# power.net
KiCad netlist of a schematic drawn in EAGLE
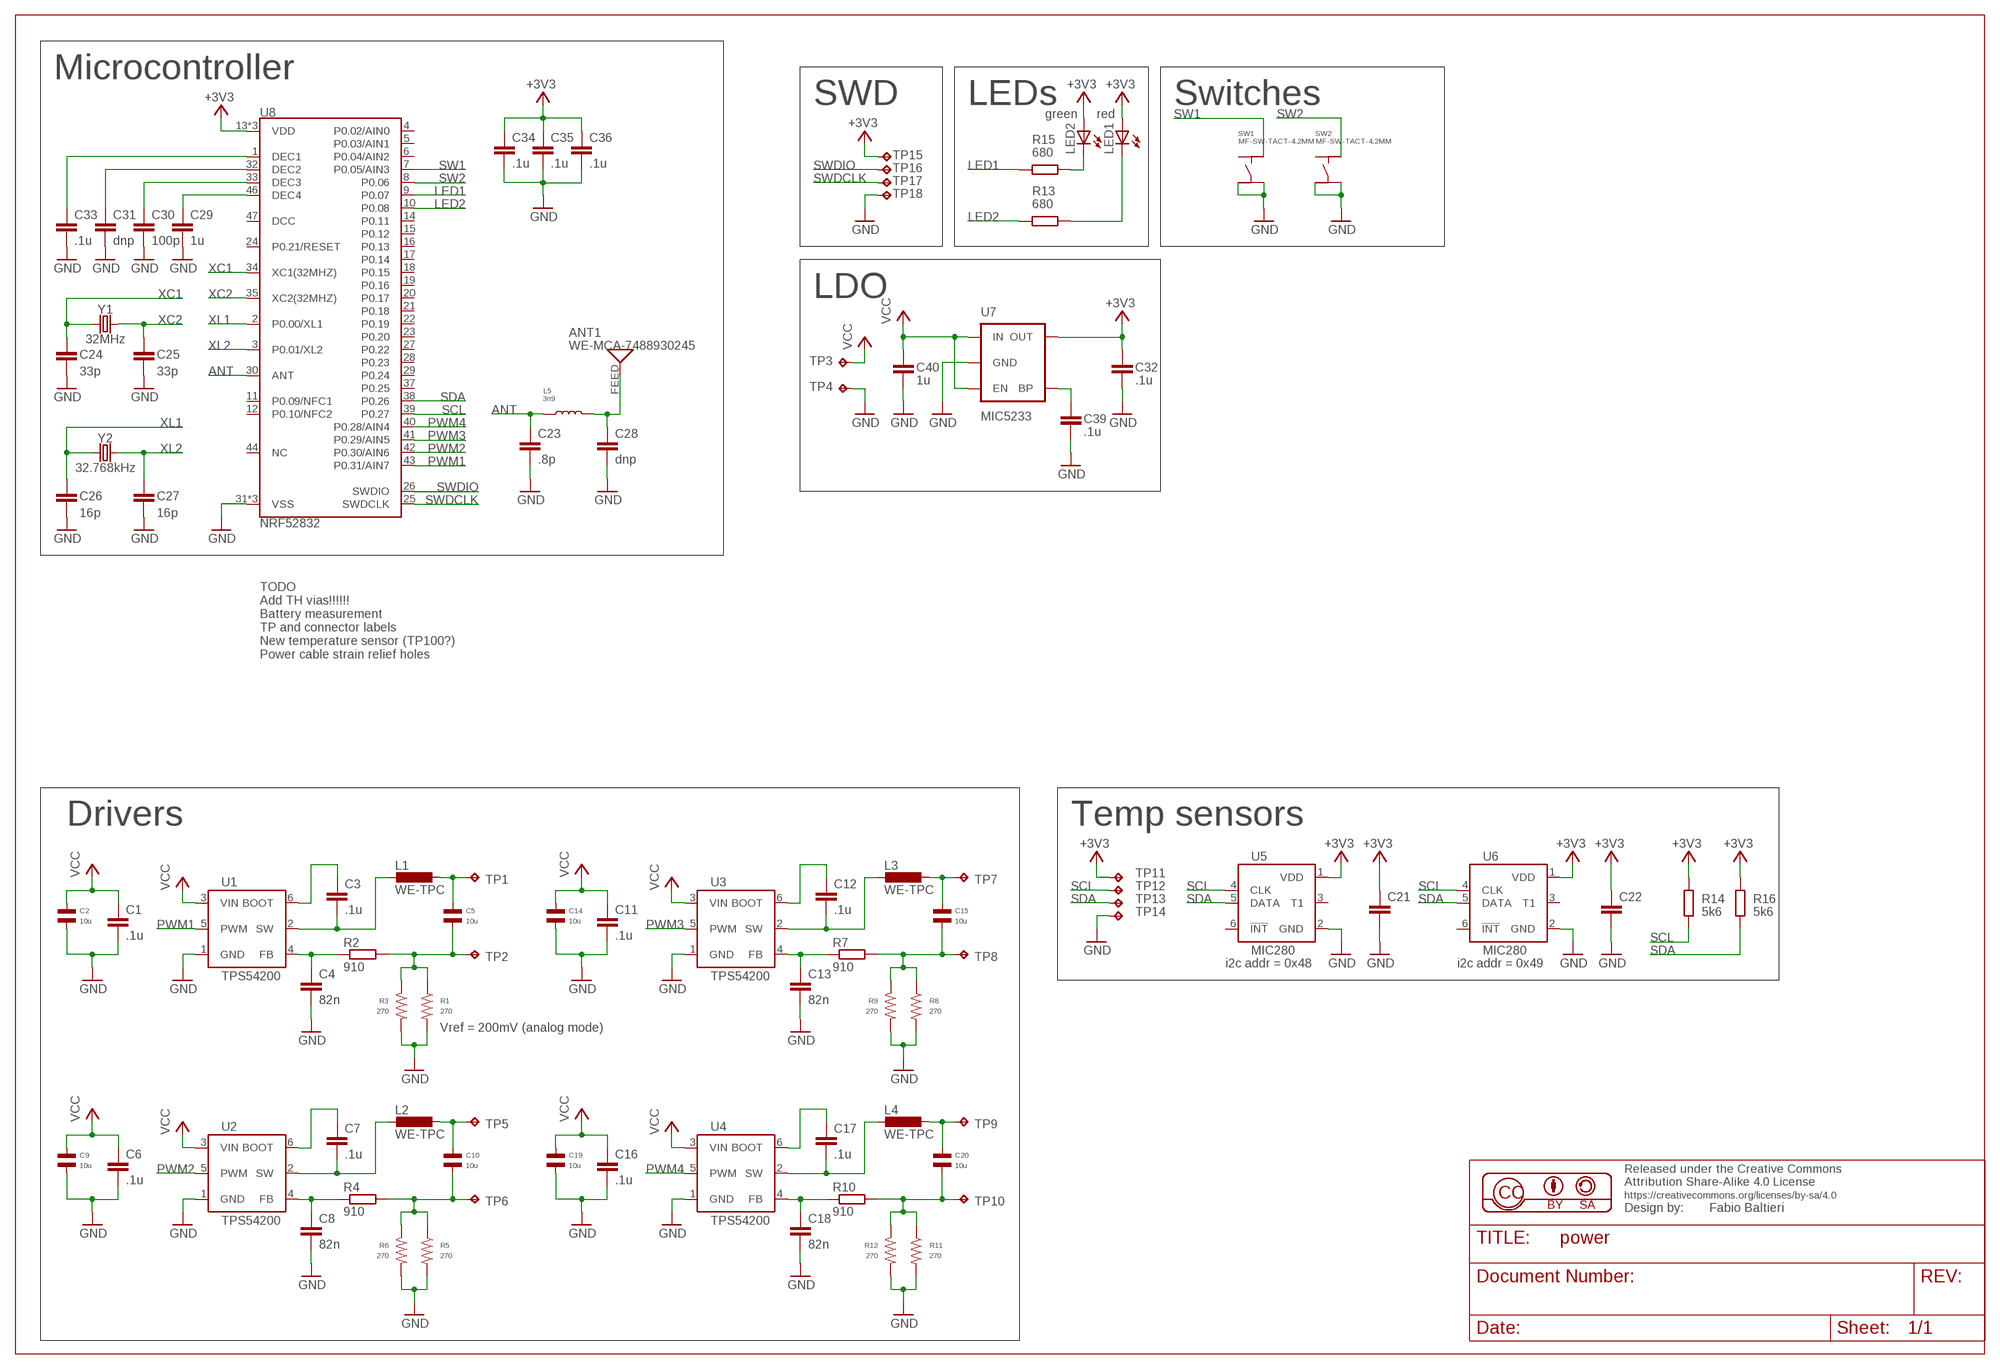
[diagram p0: schematic, sheet 1]

(export (version "E")
  (design (tool "Eeschema 10.0.6"))
  (components
    (comp (ref "ANT1")
      (value "WE-MCA-7488930245")
      (footprint "eagle-import:WE-MCA")
      (libsource (lib "eagle-import") (part "WE-MCA-7488930245"))
    )
    (comp (ref "C1")
      (value ".1u")
      (footprint "eagle-import:0603")
      (libsource (lib "eagle-import") (part "C0603"))
    )
    (comp (ref "C2")
      (value "10u")
      (footprint "eagle-import:C1206")
      (libsource (lib "eagle-import") (part "CAPACITOR_NP_1206"))
    )
    (comp (ref "C3")
      (value ".1u")
      (footprint "eagle-import:0603")
      (libsource (lib "eagle-import") (part "C0603"))
    )
    (comp (ref "C4")
      (value "82n")
      (footprint "eagle-import:0603")
      (libsource (lib "eagle-import") (part "C0603"))
    )
    (comp (ref "C5")
      (value "10u")
      (footprint "eagle-import:C1206")
      (libsource (lib "eagle-import") (part "CAPACITOR_NP_1206"))
    )
    (comp (ref "C6")
      (value ".1u")
      (footprint "eagle-import:0603")
      (libsource (lib "eagle-import") (part "C0603"))
    )
    (comp (ref "C7")
      (value ".1u")
      (footprint "eagle-import:0603")
      (libsource (lib "eagle-import") (part "C0603"))
    )
    (comp (ref "C8")
      (value "82n")
      (footprint "eagle-import:0603")
      (libsource (lib "eagle-import") (part "C0603"))
    )
    (comp (ref "C9")
      (value "10u")
      (footprint "eagle-import:C1206")
      (libsource (lib "eagle-import") (part "CAPACITOR_NP_1206"))
    )
    (comp (ref "C10")
      (value "10u")
      (footprint "eagle-import:C1206")
      (libsource (lib "eagle-import") (part "CAPACITOR_NP_1206"))
    )
    (comp (ref "C11")
      (value ".1u")
      (footprint "eagle-import:0603")
      (libsource (lib "eagle-import") (part "C0603"))
    )
    (comp (ref "C12")
      (value ".1u")
      (footprint "eagle-import:0603")
      (libsource (lib "eagle-import") (part "C0603"))
    )
    (comp (ref "C13")
      (value "82n")
      (footprint "eagle-import:0603")
      (libsource (lib "eagle-import") (part "C0603"))
    )
    (comp (ref "C14")
      (value "10u")
      (footprint "eagle-import:C1206")
      (libsource (lib "eagle-import") (part "CAPACITOR_NP_1206"))
    )
    (comp (ref "C15")
      (value "10u")
      (footprint "eagle-import:C1206")
      (libsource (lib "eagle-import") (part "CAPACITOR_NP_1206"))
    )
    (comp (ref "C16")
      (value ".1u")
      (footprint "eagle-import:0603")
      (libsource (lib "eagle-import") (part "C0603"))
    )
    (comp (ref "C17")
      (value ".1u")
      (footprint "eagle-import:0603")
      (libsource (lib "eagle-import") (part "C0603"))
    )
    (comp (ref "C18")
      (value "82n")
      (footprint "eagle-import:0603")
      (libsource (lib "eagle-import") (part "C0603"))
    )
    (comp (ref "C19")
      (value "10u")
      (footprint "eagle-import:C1206")
      (libsource (lib "eagle-import") (part "CAPACITOR_NP_1206"))
    )
    (comp (ref "C20")
      (value "10u")
      (footprint "eagle-import:C1206")
      (libsource (lib "eagle-import") (part "CAPACITOR_NP_1206"))
    )
    (comp (ref "C21")
      (value "C0603")
      (footprint "eagle-import:0603")
      (libsource (lib "eagle-import") (part "C0603"))
    )
    (comp (ref "C22")
      (value "C0603")
      (footprint "eagle-import:0603")
      (libsource (lib "eagle-import") (part "C0603"))
    )
    (comp (ref "C23")
      (value ".8p")
      (footprint "eagle-import:0603")
      (libsource (lib "eagle-import") (part "C0603"))
    )
    (comp (ref "C24")
      (value "33p")
      (footprint "eagle-import:0603")
      (libsource (lib "eagle-import") (part "C0603"))
    )
    (comp (ref "C25")
      (value "33p")
      (footprint "eagle-import:0603")
      (libsource (lib "eagle-import") (part "C0603"))
    )
    (comp (ref "C26")
      (value "16p")
      (footprint "eagle-import:0603")
      (libsource (lib "eagle-import") (part "C0603"))
    )
    (comp (ref "C27")
      (value "16p")
      (footprint "eagle-import:0603")
      (libsource (lib "eagle-import") (part "C0603"))
    )
    (comp (ref "C28")
      (value "dnp")
      (footprint "eagle-import:0603")
      (libsource (lib "eagle-import") (part "C0603"))
    )
    (comp (ref "C29")
      (value "1u")
      (footprint "eagle-import:0603")
      (libsource (lib "eagle-import") (part "C0603"))
    )
    (comp (ref "C30")
      (value "100p")
      (footprint "eagle-import:0603")
      (libsource (lib "eagle-import") (part "C0603"))
    )
    (comp (ref "C31")
      (value "dnp")
      (footprint "eagle-import:0603")
      (libsource (lib "eagle-import") (part "C0603"))
    )
    (comp (ref "C32")
      (value ".1u")
      (footprint "eagle-import:0603")
      (libsource (lib "eagle-import") (part "C0603"))
    )
    (comp (ref "C33")
      (value ".1u")
      (footprint "eagle-import:0603")
      (libsource (lib "eagle-import") (part "C0603"))
    )
    (comp (ref "C34")
      (value ".1u")
      (footprint "eagle-import:0603")
      (libsource (lib "eagle-import") (part "C0603"))
    )
    (comp (ref "C35")
      (value ".1u")
      (footprint "eagle-import:0603")
      (libsource (lib "eagle-import") (part "C0603"))
    )
    (comp (ref "C36")
      (value ".1u")
      (footprint "eagle-import:0603")
      (libsource (lib "eagle-import") (part "C0603"))
    )
    (comp (ref "C39")
      (value ".1u")
      (footprint "eagle-import:0603")
      (libsource (lib "eagle-import") (part "C0603"))
    )
    (comp (ref "C40")
      (value "1u")
      (footprint "eagle-import:0603")
      (libsource (lib "eagle-import") (part "C0603"))
    )
    (comp (ref "L1")
      (value "WE-TPC")
      (footprint "eagle-import:WE-TPC_INDUCTOR")
      (libsource (lib "eagle-import") (part "WE-TPC"))
    )
    (comp (ref "L2")
      (value "WE-TPC")
      (footprint "eagle-import:WE-TPC_INDUCTOR")
      (libsource (lib "eagle-import") (part "WE-TPC"))
    )
    (comp (ref "L3")
      (value "WE-TPC")
      (footprint "eagle-import:WE-TPC_INDUCTOR")
      (libsource (lib "eagle-import") (part "WE-TPC"))
    )
    (comp (ref "L4")
      (value "WE-TPC")
      (footprint "eagle-import:WE-TPC_INDUCTOR")
      (libsource (lib "eagle-import") (part "WE-TPC"))
    )
    (comp (ref "L5")
      (value "3n9")
      (footprint "eagle-import:L0603")
      (libsource (lib "eagle-import") (part "INDUCTOR_0603"))
    )
    (comp (ref "LED1")
      (value "LEDSML0805")
      (footprint "eagle-import:SML0805")
      (libsource (lib "eagle-import") (part "LEDSML0805"))
    )
    (comp (ref "LED2")
      (value "LEDSML0805")
      (footprint "eagle-import:SML0805")
      (libsource (lib "eagle-import") (part "LEDSML0805"))
    )
    (comp (ref "R1")
      (value "270")
      (footprint "eagle-import:R0805")
      (libsource (lib "eagle-import") (part "RESISTOR_0805"))
    )
    (comp (ref "R2")
      (value "910")
      (footprint "eagle-import:0603")
      (libsource (lib "eagle-import") (part "R0603"))
    )
    (comp (ref "R3")
      (value "270")
      (footprint "eagle-import:R0805")
      (libsource (lib "eagle-import") (part "RESISTOR_0805"))
    )
    (comp (ref "R4")
      (value "910")
      (footprint "eagle-import:0603")
      (libsource (lib "eagle-import") (part "R0603"))
    )
    (comp (ref "R5")
      (value "270")
      (footprint "eagle-import:R0805")
      (libsource (lib "eagle-import") (part "RESISTOR_0805"))
    )
    (comp (ref "R6")
      (value "270")
      (footprint "eagle-import:R0805")
      (libsource (lib "eagle-import") (part "RESISTOR_0805"))
    )
    (comp (ref "R7")
      (value "910")
      (footprint "eagle-import:0603")
      (libsource (lib "eagle-import") (part "R0603"))
    )
    (comp (ref "R8")
      (value "270")
      (footprint "eagle-import:R0805")
      (libsource (lib "eagle-import") (part "RESISTOR_0805"))
    )
    (comp (ref "R9")
      (value "270")
      (footprint "eagle-import:R0805")
      (libsource (lib "eagle-import") (part "RESISTOR_0805"))
    )
    (comp (ref "R10")
      (value "910")
      (footprint "eagle-import:0603")
      (libsource (lib "eagle-import") (part "R0603"))
    )
    (comp (ref "R11")
      (value "270")
      (footprint "eagle-import:R0805")
      (libsource (lib "eagle-import") (part "RESISTOR_0805"))
    )
    (comp (ref "R12")
      (value "270")
      (footprint "eagle-import:R0805")
      (libsource (lib "eagle-import") (part "RESISTOR_0805"))
    )
    (comp (ref "R13")
      (value "680")
      (footprint "eagle-import:0603")
      (libsource (lib "eagle-import") (part "R0603"))
    )
    (comp (ref "R14")
      (value "5k6")
      (footprint "eagle-import:0603")
      (libsource (lib "eagle-import") (part "R0603"))
    )
    (comp (ref "R15")
      (value "680")
      (footprint "eagle-import:0603")
      (libsource (lib "eagle-import") (part "R0603"))
    )
    (comp (ref "R16")
      (value "5k6")
      (footprint "eagle-import:0603")
      (libsource (lib "eagle-import") (part "R0603"))
    )
    (comp (ref "SW1")
      (value "MF-SW-TACT-4.2MM")
      (footprint "eagle-import:TACT4.2MM")
      (fields (field (name "HOUSEPART") "YES"))
      (libsource (lib "eagle-import") (part "TACT_4.2MM"))
    )
    (comp (ref "SW2")
      (value "MF-SW-TACT-4.2MM")
      (footprint "eagle-import:TACT4.2MM")
      (fields (field (name "HOUSEPART") "YES"))
      (libsource (lib "eagle-import") (part "TACT_4.2MM"))
    )
    (comp (ref "TP1")
      (value "TPTP18R")
      (footprint "eagle-import:TP18R")
      (libsource (lib "eagle-import") (part "testpad_385_TPTP18R"))
    )
    (comp (ref "TP2")
      (value "TPTP18R")
      (footprint "eagle-import:TP18R")
      (libsource (lib "eagle-import") (part "testpad_385_TPTP18R"))
    )
    (comp (ref "TP3")
      (value "TPTP18R")
      (footprint "eagle-import:TP18R")
      (libsource (lib "eagle-import") (part "testpad_385_TPTP18R"))
    )
    (comp (ref "TP4")
      (value "TPTP18R")
      (footprint "eagle-import:TP18R")
      (libsource (lib "eagle-import") (part "testpad_385_TPTP18R"))
    )
    (comp (ref "TP5")
      (value "TPTP18R")
      (footprint "eagle-import:TP18R")
      (libsource (lib "eagle-import") (part "testpad_385_TPTP18R"))
    )
    (comp (ref "TP6")
      (value "TPTP18R")
      (footprint "eagle-import:TP18R")
      (libsource (lib "eagle-import") (part "testpad_385_TPTP18R"))
    )
    (comp (ref "TP7")
      (value "TPTP18R")
      (footprint "eagle-import:TP18R")
      (libsource (lib "eagle-import") (part "testpad_385_TPTP18R"))
    )
    (comp (ref "TP8")
      (value "TPTP18R")
      (footprint "eagle-import:TP18R")
      (libsource (lib "eagle-import") (part "testpad_385_TPTP18R"))
    )
    (comp (ref "TP9")
      (value "TPTP18R")
      (footprint "eagle-import:TP18R")
      (libsource (lib "eagle-import") (part "testpad_385_TPTP18R"))
    )
    (comp (ref "TP10")
      (value "TPTP18R")
      (footprint "eagle-import:TP18R")
      (libsource (lib "eagle-import") (part "testpad_385_TPTP18R"))
    )
    (comp (ref "TP11")
      (value "TPTP14R")
      (footprint "eagle-import:TP14R")
      (libsource (lib "eagle-import") (part "testpad_385_TPTP14R"))
    )
    (comp (ref "TP12")
      (value "TPTP14R")
      (footprint "eagle-import:TP14R")
      (libsource (lib "eagle-import") (part "testpad_385_TPTP14R"))
    )
    (comp (ref "TP13")
      (value "TPTP14R")
      (footprint "eagle-import:TP14R")
      (libsource (lib "eagle-import") (part "testpad_385_TPTP14R"))
    )
    (comp (ref "TP14")
      (value "TPTP14R")
      (footprint "eagle-import:TP14R")
      (libsource (lib "eagle-import") (part "testpad_385_TPTP14R"))
    )
    (comp (ref "TP15")
      (value "TPTP12R")
      (footprint "eagle-import:TP12R")
      (libsource (lib "eagle-import") (part "TPTP12R"))
    )
    (comp (ref "TP16")
      (value "TPTP12R")
      (footprint "eagle-import:TP12R")
      (libsource (lib "eagle-import") (part "TPTP12R"))
    )
    (comp (ref "TP17")
      (value "TPTP12R")
      (footprint "eagle-import:TP12R")
      (libsource (lib "eagle-import") (part "TPTP12R"))
    )
    (comp (ref "TP18")
      (value "TPTP12R")
      (footprint "eagle-import:TP12R")
      (libsource (lib "eagle-import") (part "TPTP12R"))
    )
    (comp (ref "U1")
      (value "TPS54200")
      (footprint "eagle-import:SOT23-6L")
      (libsource (lib "eagle-import") (part "TPS54200"))
    )
    (comp (ref "U2")
      (value "TPS54200")
      (footprint "eagle-import:SOT23-6L")
      (libsource (lib "eagle-import") (part "TPS54200"))
    )
    (comp (ref "U3")
      (value "TPS54200")
      (footprint "eagle-import:SOT23-6L")
      (libsource (lib "eagle-import") (part "TPS54200"))
    )
    (comp (ref "U4")
      (value "TPS54200")
      (footprint "eagle-import:SOT23-6L")
      (libsource (lib "eagle-import") (part "TPS54200"))
    )
    (comp (ref "U5")
      (value "MIC280")
      (footprint "eagle-import:SOT23-6L")
      (libsource (lib "eagle-import") (part "MIC280"))
    )
    (comp (ref "U6")
      (value "MIC280")
      (footprint "eagle-import:SOT23-6L")
      (libsource (lib "eagle-import") (part "MIC280"))
    )
    (comp (ref "U7")
      (value "MIC5233")
      (footprint "eagle-import:SOT23-5")
      (libsource (lib "eagle-import") (part "V_REG_LDOSMD"))
    )
    (comp (ref "U8")
      (value "NRF52832")
      (footprint "eagle-import:QFN48-6X6MM")
      (libsource (lib "eagle-import") (part "NRF52832"))
    )
    (comp (ref "Y1")
      (value "32MHz")
      (footprint "eagle-import:CRYSTAL-SMD-3.2X2.5MM")
      (libsource (lib "eagle-import") (part "CRYSTALSMD-3.2X2.5"))
    )
    (comp (ref "Y2")
      (value "32.768kHz")
      (footprint "eagle-import:CRYSTAL-SMD-3.2X1.5MM")
      (libsource (lib "eagle-import") (part "CRYSTAL-32.768KHZSMD-3.2X1.5"))
    )
  )
  (nets
    (net (code "1") (name "+3V3") (class "Default")
      (node (ref "C21") (pin "1") (pinfunction "1_1") (pintype "passive"))
      (node (ref "C22") (pin "1") (pinfunction "1_1") (pintype "passive"))
      (node (ref "C32") (pin "1") (pinfunction "1_1") (pintype "passive"))
      (node (ref "C34") (pin "1") (pinfunction "1_1") (pintype "passive"))
      (node (ref "C35") (pin "1") (pinfunction "1_1") (pintype "passive"))
      (node (ref "C36") (pin "1") (pinfunction "1_1") (pintype "passive"))
      (node (ref "LED1") (pin "A") (pinfunction "A_A") (pintype "passive"))
      (node (ref "LED2") (pin "A") (pinfunction "A_A") (pintype "passive"))
      (node (ref "R14") (pin "1") (pinfunction "1_1") (pintype "passive"))
      (node (ref "R16") (pin "1") (pinfunction "1_1") (pintype "passive"))
      (node (ref "TP11") (pin "TP") (pinfunction "TP_TP") (pintype "input"))
      (node (ref "TP15") (pin "TP") (pinfunction "TP_TP") (pintype "input"))
      (node (ref "U5") (pin "1") (pinfunction "VDD_1") (pintype "bidirectional"))
      (node (ref "U6") (pin "1") (pinfunction "VDD_1") (pintype "bidirectional"))
      (node (ref "U7") (pin "5") (pinfunction "OUT_5") (pintype "passive"))
      (node (ref "U8") (pin "13") (pinfunction "VDD_13") (pintype "bidirectional"))
      (node (ref "U8") (pin "36") (pinfunction "VDD_36") (pintype "bidirectional"))
      (node (ref "U8") (pin "48") (pinfunction "VDD_48") (pintype "bidirectional"))
    )
    (net (code "2") (name "/ANT") (class "Default")
      (node (ref "C23") (pin "1") (pinfunction "1_1") (pintype "passive"))
      (node (ref "L5") (pin "P$1") (pinfunction "P$1_P$1") (pintype "passive"))
      (node (ref "U8") (pin "30") (pinfunction "ANT_30") (pintype "bidirectional"))
    )
    (net (code "3") (name "/LED1") (class "Default")
      (node (ref "R15") (pin "2") (pinfunction "2_2") (pintype "passive"))
      (node (ref "U8") (pin "9") (pinfunction "P0.07_9") (pintype "bidirectional"))
    )
    (net (code "4") (name "/LED2") (class "Default")
      (node (ref "R13") (pin "2") (pinfunction "2_2") (pintype "passive"))
      (node (ref "U8") (pin "10") (pinfunction "P0.08_10") (pintype "bidirectional"))
    )
    (net (code "5") (name "/PWM1") (class "Default")
      (node (ref "U1") (pin "5") (pinfunction "PWM_5") (pintype "bidirectional"))
      (node (ref "U8") (pin "43") (pinfunction "P0.31/AIN7_43") (pintype "bidirectional"))
    )
    (net (code "6") (name "/PWM2") (class "Default")
      (node (ref "U2") (pin "5") (pinfunction "PWM_5") (pintype "bidirectional"))
      (node (ref "U8") (pin "42") (pinfunction "P0.30/AIN6_42") (pintype "bidirectional"))
    )
    (net (code "7") (name "/PWM3") (class "Default")
      (node (ref "U3") (pin "5") (pinfunction "PWM_5") (pintype "bidirectional"))
      (node (ref "U8") (pin "41") (pinfunction "P0.29/AIN5_41") (pintype "bidirectional"))
    )
    (net (code "8") (name "/PWM4") (class "Default")
      (node (ref "U4") (pin "5") (pinfunction "PWM_5") (pintype "bidirectional"))
      (node (ref "U8") (pin "40") (pinfunction "P0.28/AIN4_40") (pintype "bidirectional"))
    )
    (net (code "9") (name "/SCL") (class "Default")
      (node (ref "R14") (pin "2") (pinfunction "2_2") (pintype "passive"))
      (node (ref "TP12") (pin "TP") (pinfunction "TP_TP") (pintype "input"))
      (node (ref "U5") (pin "4") (pinfunction "CLK_4") (pintype "bidirectional"))
      (node (ref "U6") (pin "4") (pinfunction "CLK_4") (pintype "bidirectional"))
      (node (ref "U8") (pin "39") (pinfunction "P0.27_39") (pintype "bidirectional"))
    )
    (net (code "10") (name "/SDA") (class "Default")
      (node (ref "R16") (pin "2") (pinfunction "2_2") (pintype "passive"))
      (node (ref "TP13") (pin "TP") (pinfunction "TP_TP") (pintype "input"))
      (node (ref "U5") (pin "5") (pinfunction "DATA_5") (pintype "bidirectional"))
      (node (ref "U6") (pin "5") (pinfunction "DATA_5") (pintype "bidirectional"))
      (node (ref "U8") (pin "38") (pinfunction "P0.26_38") (pintype "bidirectional"))
    )
    (net (code "11") (name "/SW1") (class "Default")
      (node (ref "SW1") (pin "P$2") (pinfunction "P$2_P$2") (pintype "bidirectional"))
      (node (ref "U8") (pin "7") (pinfunction "P0.05/AIN3_7") (pintype "bidirectional"))
    )
    (net (code "12") (name "/SW2") (class "Default")
      (node (ref "SW2") (pin "P$2") (pinfunction "P$2_P$2") (pintype "bidirectional"))
      (node (ref "U8") (pin "8") (pinfunction "P0.06_8") (pintype "bidirectional"))
    )
    (net (code "13") (name "/SWDCLK") (class "Default")
      (node (ref "TP17") (pin "TP") (pinfunction "TP_TP") (pintype "input"))
      (node (ref "U8") (pin "25") (pinfunction "SWDCLK_25") (pintype "bidirectional"))
    )
    (net (code "14") (name "/SWDIO") (class "Default")
      (node (ref "TP16") (pin "TP") (pinfunction "TP_TP") (pintype "input"))
      (node (ref "U8") (pin "26") (pinfunction "SWDIO_26") (pintype "bidirectional"))
    )
    (net (code "15") (name "/XC1") (class "Default")
      (node (ref "C24") (pin "1") (pinfunction "1_1") (pintype "passive"))
      (node (ref "U8") (pin "34") (pinfunction "XC1(32MHZ)_34") (pintype "bidirectional"))
      (node (ref "Y1") (pin "1") (pinfunction "1_1") (pintype "passive"))
    )
    (net (code "16") (name "/XC2") (class "Default")
      (node (ref "C25") (pin "1") (pinfunction "1_1") (pintype "passive"))
      (node (ref "U8") (pin "35") (pinfunction "XC2(32MHZ)_35") (pintype "bidirectional"))
      (node (ref "Y1") (pin "3") (pinfunction "2_3") (pintype "passive"))
    )
    (net (code "17") (name "/XL1") (class "Default")
      (node (ref "C26") (pin "1") (pinfunction "1_1") (pintype "passive"))
      (node (ref "U8") (pin "2") (pinfunction "P0.00/XL1_2") (pintype "bidirectional"))
      (node (ref "Y2") (pin "P$1") (pinfunction "1_P$1") (pintype "passive"))
    )
    (net (code "18") (name "/XL2") (class "Default")
      (node (ref "C27") (pin "1") (pinfunction "1_1") (pintype "passive"))
      (node (ref "U8") (pin "3") (pinfunction "P0.01/XL2_3") (pintype "bidirectional"))
      (node (ref "Y2") (pin "P$2") (pinfunction "2_P$2") (pintype "passive"))
    )
    (net (code "19") (name "GND") (class "Default")
      (node (ref "C1") (pin "2") (pinfunction "2_2") (pintype "passive"))
      (node (ref "C11") (pin "2") (pinfunction "2_2") (pintype "passive"))
      (node (ref "C13") (pin "2") (pinfunction "2_2") (pintype "passive"))
      (node (ref "C14") (pin "P$2") (pinfunction "P$2_P$2") (pintype "passive"))
      (node (ref "C16") (pin "2") (pinfunction "2_2") (pintype "passive"))
      (node (ref "C18") (pin "2") (pinfunction "2_2") (pintype "passive"))
      (node (ref "C19") (pin "P$2") (pinfunction "P$2_P$2") (pintype "passive"))
      (node (ref "C2") (pin "P$2") (pinfunction "P$2_P$2") (pintype "passive"))
      (node (ref "C21") (pin "2") (pinfunction "2_2") (pintype "passive"))
      (node (ref "C22") (pin "2") (pinfunction "2_2") (pintype "passive"))
      (node (ref "C23") (pin "2") (pinfunction "2_2") (pintype "passive"))
      (node (ref "C24") (pin "2") (pinfunction "2_2") (pintype "passive"))
      (node (ref "C25") (pin "2") (pinfunction "2_2") (pintype "passive"))
      (node (ref "C26") (pin "2") (pinfunction "2_2") (pintype "passive"))
      (node (ref "C27") (pin "2") (pinfunction "2_2") (pintype "passive"))
      (node (ref "C28") (pin "2") (pinfunction "2_2") (pintype "passive"))
      (node (ref "C29") (pin "2") (pinfunction "2_2") (pintype "passive"))
      (node (ref "C30") (pin "2") (pinfunction "2_2") (pintype "passive"))
      (node (ref "C31") (pin "2") (pinfunction "2_2") (pintype "passive"))
      (node (ref "C32") (pin "2") (pinfunction "2_2") (pintype "passive"))
      (node (ref "C33") (pin "2") (pinfunction "2_2") (pintype "passive"))
      (node (ref "C34") (pin "2") (pinfunction "2_2") (pintype "passive"))
      (node (ref "C35") (pin "2") (pinfunction "2_2") (pintype "passive"))
      (node (ref "C36") (pin "2") (pinfunction "2_2") (pintype "passive"))
      (node (ref "C39") (pin "2") (pinfunction "2_2") (pintype "passive"))
      (node (ref "C4") (pin "2") (pinfunction "2_2") (pintype "passive"))
      (node (ref "C40") (pin "2") (pinfunction "2_2") (pintype "passive"))
      (node (ref "C6") (pin "2") (pinfunction "2_2") (pintype "passive"))
      (node (ref "C8") (pin "2") (pinfunction "2_2") (pintype "passive"))
      (node (ref "C9") (pin "P$2") (pinfunction "P$2_P$2") (pintype "passive"))
      (node (ref "R1") (pin "P$2") (pinfunction "P$2_P$2") (pintype "passive"))
      (node (ref "R11") (pin "P$2") (pinfunction "P$2_P$2") (pintype "passive"))
      (node (ref "R12") (pin "P$2") (pinfunction "P$2_P$2") (pintype "passive"))
      (node (ref "R3") (pin "P$2") (pinfunction "P$2_P$2") (pintype "passive"))
      (node (ref "R5") (pin "P$2") (pinfunction "P$2_P$2") (pintype "passive"))
      (node (ref "R6") (pin "P$2") (pinfunction "P$2_P$2") (pintype "passive"))
      (node (ref "R8") (pin "P$2") (pinfunction "P$2_P$2") (pintype "passive"))
      (node (ref "R9") (pin "P$2") (pinfunction "P$2_P$2") (pintype "passive"))
      (node (ref "SW1") (pin "P$3") (pinfunction "P$3_P$3") (pintype "bidirectional"))
      (node (ref "SW1") (pin "P$4") (pinfunction "P$4_P$4") (pintype "bidirectional"))
      (node (ref "SW2") (pin "P$3") (pinfunction "P$3_P$3") (pintype "bidirectional"))
      (node (ref "SW2") (pin "P$4") (pinfunction "P$4_P$4") (pintype "bidirectional"))
      (node (ref "TP14") (pin "TP") (pinfunction "TP_TP") (pintype "input"))
      (node (ref "TP18") (pin "TP") (pinfunction "TP_TP") (pintype "input"))
      (node (ref "TP4") (pin "TP") (pinfunction "TP_TP") (pintype "input"))
      (node (ref "U1") (pin "1") (pinfunction "GND_1") (pintype "bidirectional"))
      (node (ref "U2") (pin "1") (pinfunction "GND_1") (pintype "bidirectional"))
      (node (ref "U3") (pin "1") (pinfunction "GND_1") (pintype "bidirectional"))
      (node (ref "U4") (pin "1") (pinfunction "GND_1") (pintype "bidirectional"))
      (node (ref "U5") (pin "2") (pinfunction "GND_2") (pintype "bidirectional"))
      (node (ref "U6") (pin "2") (pinfunction "GND_2") (pintype "bidirectional"))
      (node (ref "U7") (pin "2") (pinfunction "GND_2") (pintype "input"))
      (node (ref "U8") (pin "31") (pinfunction "VSS_31") (pintype "bidirectional"))
      (node (ref "U8") (pin "45") (pinfunction "VSS_45") (pintype "bidirectional"))
      (node (ref "U8") (pin "EP") (pinfunction "VSS_EP") (pintype "bidirectional"))
    )
    (net (code "20") (name "Net-(ANT1-P$1)") (class "Default")
      (node (ref "ANT1") (pin "FEED") (pinfunction "P$1_FEED") (pintype "bidirectional"))
      (node (ref "C28") (pin "1") (pinfunction "1_1") (pintype "passive"))
      (node (ref "L5") (pin "P$2") (pinfunction "P$2_P$2") (pintype "passive"))
    )
    (net (code "21") (name "Net-(C5-PadP$2)") (class "Default")
      (node (ref "C5") (pin "P$2") (pinfunction "P$2_P$2") (pintype "passive"))
      (node (ref "R1") (pin "P$1") (pinfunction "P$1_P$1") (pintype "passive"))
      (node (ref "R2") (pin "2") (pinfunction "2_2") (pintype "passive"))
      (node (ref "R3") (pin "P$1") (pinfunction "P$1_P$1") (pintype "passive"))
      (node (ref "TP2") (pin "TP") (pinfunction "TP_TP") (pintype "input"))
    )
    (net (code "22") (name "Net-(C10-PadP$2)") (class "Default")
      (node (ref "C10") (pin "P$2") (pinfunction "P$2_P$2") (pintype "passive"))
      (node (ref "R4") (pin "2") (pinfunction "2_2") (pintype "passive"))
      (node (ref "R5") (pin "P$1") (pinfunction "P$1_P$1") (pintype "passive"))
      (node (ref "R6") (pin "P$1") (pinfunction "P$1_P$1") (pintype "passive"))
      (node (ref "TP6") (pin "TP") (pinfunction "TP_TP") (pintype "input"))
    )
    (net (code "23") (name "Net-(C15-PadP$2)") (class "Default")
      (node (ref "C15") (pin "P$2") (pinfunction "P$2_P$2") (pintype "passive"))
      (node (ref "R7") (pin "2") (pinfunction "2_2") (pintype "passive"))
      (node (ref "R8") (pin "P$1") (pinfunction "P$1_P$1") (pintype "passive"))
      (node (ref "R9") (pin "P$1") (pinfunction "P$1_P$1") (pintype "passive"))
      (node (ref "TP8") (pin "TP") (pinfunction "TP_TP") (pintype "input"))
    )
    (net (code "24") (name "Net-(C20-PadP$2)") (class "Default")
      (node (ref "C20") (pin "P$2") (pinfunction "P$2_P$2") (pintype "passive"))
      (node (ref "R10") (pin "2") (pinfunction "2_2") (pintype "passive"))
      (node (ref "R11") (pin "P$1") (pinfunction "P$1_P$1") (pintype "passive"))
      (node (ref "R12") (pin "P$1") (pinfunction "P$1_P$1") (pintype "passive"))
      (node (ref "TP10") (pin "TP") (pinfunction "TP_TP") (pintype "input"))
    )
    (net (code "25") (name "Net-(L1-1)") (class "Default")
      (node (ref "C3") (pin "2") (pinfunction "2_2") (pintype "passive"))
      (node (ref "L1") (pin "P$1") (pinfunction "1_P$1") (pintype "passive"))
      (node (ref "U1") (pin "2") (pinfunction "SW_2") (pintype "bidirectional"))
    )
    (net (code "26") (name "Net-(L1-2)") (class "Default")
      (node (ref "C5") (pin "P$1") (pinfunction "P$1_P$1") (pintype "passive"))
      (node (ref "L1") (pin "P$2") (pinfunction "2_P$2") (pintype "passive"))
      (node (ref "TP1") (pin "TP") (pinfunction "TP_TP") (pintype "input"))
    )
    (net (code "27") (name "Net-(L2-1)") (class "Default")
      (node (ref "C7") (pin "2") (pinfunction "2_2") (pintype "passive"))
      (node (ref "L2") (pin "P$1") (pinfunction "1_P$1") (pintype "passive"))
      (node (ref "U2") (pin "2") (pinfunction "SW_2") (pintype "bidirectional"))
    )
    (net (code "28") (name "Net-(L2-2)") (class "Default")
      (node (ref "C10") (pin "P$1") (pinfunction "P$1_P$1") (pintype "passive"))
      (node (ref "L2") (pin "P$2") (pinfunction "2_P$2") (pintype "passive"))
      (node (ref "TP5") (pin "TP") (pinfunction "TP_TP") (pintype "input"))
    )
    (net (code "29") (name "Net-(L3-1)") (class "Default")
      (node (ref "C12") (pin "2") (pinfunction "2_2") (pintype "passive"))
      (node (ref "L3") (pin "P$1") (pinfunction "1_P$1") (pintype "passive"))
      (node (ref "U3") (pin "2") (pinfunction "SW_2") (pintype "bidirectional"))
    )
    (net (code "30") (name "Net-(L3-2)") (class "Default")
      (node (ref "C15") (pin "P$1") (pinfunction "P$1_P$1") (pintype "passive"))
      (node (ref "L3") (pin "P$2") (pinfunction "2_P$2") (pintype "passive"))
      (node (ref "TP7") (pin "TP") (pinfunction "TP_TP") (pintype "input"))
    )
    (net (code "31") (name "Net-(L4-1)") (class "Default")
      (node (ref "C17") (pin "2") (pinfunction "2_2") (pintype "passive"))
      (node (ref "L4") (pin "P$1") (pinfunction "1_P$1") (pintype "passive"))
      (node (ref "U4") (pin "2") (pinfunction "SW_2") (pintype "bidirectional"))
    )
    (net (code "32") (name "Net-(L4-2)") (class "Default")
      (node (ref "C20") (pin "P$1") (pinfunction "P$1_P$1") (pintype "passive"))
      (node (ref "L4") (pin "P$2") (pinfunction "2_P$2") (pintype "passive"))
      (node (ref "TP9") (pin "TP") (pinfunction "TP_TP") (pintype "input"))
    )
    (net (code "33") (name "Net-(LED1-PadC)") (class "Default")
      (node (ref "LED1") (pin "C") (pinfunction "C_C") (pintype "passive"))
      (node (ref "R13") (pin "1") (pinfunction "1_1") (pintype "passive"))
    )
    (net (code "34") (name "Net-(LED2-PadC)") (class "Default")
      (node (ref "LED2") (pin "C") (pinfunction "C_C") (pintype "passive"))
      (node (ref "R15") (pin "1") (pinfunction "1_1") (pintype "passive"))
    )
    (net (code "35") (name "Net-(U1-BOOT)") (class "Default")
      (node (ref "C3") (pin "1") (pinfunction "1_1") (pintype "passive"))
      (node (ref "U1") (pin "6") (pinfunction "BOOT_6") (pintype "bidirectional"))
    )
    (net (code "36") (name "Net-(U1-FB)") (class "Default")
      (node (ref "C4") (pin "1") (pinfunction "1_1") (pintype "passive"))
      (node (ref "R2") (pin "1") (pinfunction "1_1") (pintype "passive"))
      (node (ref "U1") (pin "4") (pinfunction "FB_4") (pintype "bidirectional"))
    )
    (net (code "37") (name "Net-(U2-BOOT)") (class "Default")
      (node (ref "C7") (pin "1") (pinfunction "1_1") (pintype "passive"))
      (node (ref "U2") (pin "6") (pinfunction "BOOT_6") (pintype "bidirectional"))
    )
    (net (code "38") (name "Net-(U2-FB)") (class "Default")
      (node (ref "C8") (pin "1") (pinfunction "1_1") (pintype "passive"))
      (node (ref "R4") (pin "1") (pinfunction "1_1") (pintype "passive"))
      (node (ref "U2") (pin "4") (pinfunction "FB_4") (pintype "bidirectional"))
    )
    (net (code "39") (name "Net-(U3-BOOT)") (class "Default")
      (node (ref "C12") (pin "1") (pinfunction "1_1") (pintype "passive"))
      (node (ref "U3") (pin "6") (pinfunction "BOOT_6") (pintype "bidirectional"))
    )
    (net (code "40") (name "Net-(U3-FB)") (class "Default")
      (node (ref "C13") (pin "1") (pinfunction "1_1") (pintype "passive"))
      (node (ref "R7") (pin "1") (pinfunction "1_1") (pintype "passive"))
      (node (ref "U3") (pin "4") (pinfunction "FB_4") (pintype "bidirectional"))
    )
    (net (code "41") (name "Net-(U4-BOOT)") (class "Default")
      (node (ref "C17") (pin "1") (pinfunction "1_1") (pintype "passive"))
      (node (ref "U4") (pin "6") (pinfunction "BOOT_6") (pintype "bidirectional"))
    )
    (net (code "42") (name "Net-(U4-FB)") (class "Default")
      (node (ref "C18") (pin "1") (pinfunction "1_1") (pintype "passive"))
      (node (ref "R10") (pin "1") (pinfunction "1_1") (pintype "passive"))
      (node (ref "U4") (pin "4") (pinfunction "FB_4") (pintype "bidirectional"))
    )
    (net (code "43") (name "Net-(U7-BP)") (class "Default")
      (node (ref "C39") (pin "1") (pinfunction "1_1") (pintype "passive"))
      (node (ref "U7") (pin "4") (pinfunction "BP_4") (pintype "input"))
    )
    (net (code "44") (name "Net-(U8-DEC1)") (class "Default")
      (node (ref "C33") (pin "1") (pinfunction "1_1") (pintype "passive"))
      (node (ref "U8") (pin "1") (pinfunction "DEC1_1") (pintype "bidirectional"))
    )
    (net (code "45") (name "Net-(U8-DEC2)") (class "Default")
      (node (ref "C31") (pin "1") (pinfunction "1_1") (pintype "passive"))
      (node (ref "U8") (pin "32") (pinfunction "DEC2_32") (pintype "bidirectional"))
    )
    (net (code "46") (name "Net-(U8-DEC3)") (class "Default")
      (node (ref "C30") (pin "1") (pinfunction "1_1") (pintype "passive"))
      (node (ref "U8") (pin "33") (pinfunction "DEC3_33") (pintype "bidirectional"))
    )
    (net (code "47") (name "Net-(U8-DEC4)") (class "Default")
      (node (ref "C29") (pin "1") (pinfunction "1_1") (pintype "passive"))
      (node (ref "U8") (pin "46") (pinfunction "DEC4_46") (pintype "bidirectional"))
    )
    (net (code "48") (name "VCC") (class "Default")
      (node (ref "C1") (pin "1") (pinfunction "1_1") (pintype "passive"))
      (node (ref "C11") (pin "1") (pinfunction "1_1") (pintype "passive"))
      (node (ref "C14") (pin "P$1") (pinfunction "P$1_P$1") (pintype "passive"))
      (node (ref "C16") (pin "1") (pinfunction "1_1") (pintype "passive"))
      (node (ref "C19") (pin "P$1") (pinfunction "P$1_P$1") (pintype "passive"))
      (node (ref "C2") (pin "P$1") (pinfunction "P$1_P$1") (pintype "passive"))
      (node (ref "C40") (pin "1") (pinfunction "1_1") (pintype "passive"))
      (node (ref "C6") (pin "1") (pinfunction "1_1") (pintype "passive"))
      (node (ref "C9") (pin "P$1") (pinfunction "P$1_P$1") (pintype "passive"))
      (node (ref "TP3") (pin "TP") (pinfunction "TP_TP") (pintype "input"))
      (node (ref "U1") (pin "3") (pinfunction "VIN_3") (pintype "bidirectional"))
      (node (ref "U2") (pin "3") (pinfunction "VIN_3") (pintype "bidirectional"))
      (node (ref "U3") (pin "3") (pinfunction "VIN_3") (pintype "bidirectional"))
      (node (ref "U4") (pin "3") (pinfunction "VIN_3") (pintype "bidirectional"))
      (node (ref "U7") (pin "1") (pinfunction "IN_1") (pintype "input"))
      (node (ref "U7") (pin "3") (pinfunction "EN_3") (pintype "input"))
    )
    (net (code "49") (name "unconnected-(SW1-PadP$1)") (class "Default")
      (node (ref "SW1") (pin "P$1") (pinfunction "P$1_P$1") (pintype "bidirectional"))
    )
    (net (code "50") (name "unconnected-(SW2-PadP$1)") (class "Default")
      (node (ref "SW2") (pin "P$1") (pinfunction "P$1_P$1") (pintype "bidirectional"))
    )
    (net (code "51") (name "unconnected-(U5-T1-Pad3)") (class "Default")
      (node (ref "U5") (pin "3") (pinfunction "T1_3") (pintype "bidirectional"))
    )
    (net (code "52") (name "unconnected-(U5-~{INT}-Pad6)") (class "Default")
      (node (ref "U5") (pin "6") (pinfunction "~{INT}_6") (pintype "bidirectional"))
    )
    (net (code "53") (name "unconnected-(U6-T1-Pad3)") (class "Default")
      (node (ref "U6") (pin "3") (pinfunction "T1_3") (pintype "bidirectional"))
    )
    (net (code "54") (name "unconnected-(U6-~{INT}-Pad6)") (class "Default")
      (node (ref "U6") (pin "6") (pinfunction "~{INT}_6") (pintype "bidirectional"))
    )
    (net (code "55") (name "unconnected-(U8-DCC-Pad47)") (class "Default")
      (node (ref "U8") (pin "47") (pinfunction "DCC_47") (pintype "bidirectional"))
    )
    (net (code "56") (name "unconnected-(U8-NC-Pad44)") (class "Default")
      (node (ref "U8") (pin "44") (pinfunction "NC_44") (pintype "bidirectional"))
    )
    (net (code "57") (name "unconnected-(U8-P0.02{slash}AIN0-Pad4)") (class "Default")
      (node (ref "U8") (pin "4") (pinfunction "P0.02/AIN0_4") (pintype "bidirectional"))
    )
    (net (code "58") (name "unconnected-(U8-P0.03{slash}AIN1-Pad5)") (class "Default")
      (node (ref "U8") (pin "5") (pinfunction "P0.03/AIN1_5") (pintype "bidirectional"))
    )
    (net (code "59") (name "unconnected-(U8-P0.04{slash}AIN2-Pad6)") (class "Default")
      (node (ref "U8") (pin "6") (pinfunction "P0.04/AIN2_6") (pintype "bidirectional"))
    )
    (net (code "60") (name "unconnected-(U8-P0.09{slash}NFC1-Pad11)") (class "Default")
      (node (ref "U8") (pin "11") (pinfunction "P0.09/NFC1_11") (pintype "bidirectional"))
    )
    (net (code "61") (name "unconnected-(U8-P0.10{slash}NFC2-Pad12)") (class "Default")
      (node (ref "U8") (pin "12") (pinfunction "P0.10/NFC2_12") (pintype "bidirectional"))
    )
    (net (code "62") (name "unconnected-(U8-P0.11-Pad14)") (class "Default")
      (node (ref "U8") (pin "14") (pinfunction "P0.11_14") (pintype "bidirectional"))
    )
    (net (code "63") (name "unconnected-(U8-P0.12-Pad15)") (class "Default")
      (node (ref "U8") (pin "15") (pinfunction "P0.12_15") (pintype "bidirectional"))
    )
    (net (code "64") (name "unconnected-(U8-P0.13-Pad16)") (class "Default")
      (node (ref "U8") (pin "16") (pinfunction "P0.13_16") (pintype "bidirectional"))
    )
    (net (code "65") (name "unconnected-(U8-P0.14-Pad17)") (class "Default")
      (node (ref "U8") (pin "17") (pinfunction "P0.14_17") (pintype "bidirectional"))
    )
    (net (code "66") (name "unconnected-(U8-P0.15-Pad18)") (class "Default")
      (node (ref "U8") (pin "18") (pinfunction "P0.15_18") (pintype "bidirectional"))
    )
    (net (code "67") (name "unconnected-(U8-P0.16-Pad19)") (class "Default")
      (node (ref "U8") (pin "19") (pinfunction "P0.16_19") (pintype "bidirectional"))
    )
    (net (code "68") (name "unconnected-(U8-P0.17-Pad20)") (class "Default")
      (node (ref "U8") (pin "20") (pinfunction "P0.17_20") (pintype "bidirectional"))
    )
    (net (code "69") (name "unconnected-(U8-P0.18-Pad21)") (class "Default")
      (node (ref "U8") (pin "21") (pinfunction "P0.18_21") (pintype "bidirectional"))
    )
    (net (code "70") (name "unconnected-(U8-P0.19-Pad22)") (class "Default")
      (node (ref "U8") (pin "22") (pinfunction "P0.19_22") (pintype "bidirectional"))
    )
    (net (code "71") (name "unconnected-(U8-P0.20-Pad23)") (class "Default")
      (node (ref "U8") (pin "23") (pinfunction "P0.20_23") (pintype "bidirectional"))
    )
    (net (code "72") (name "unconnected-(U8-P0.21{slash}RESET-Pad24)") (class "Default")
      (node (ref "U8") (pin "24") (pinfunction "P0.21/RESET_24") (pintype "bidirectional"))
    )
    (net (code "73") (name "unconnected-(U8-P0.22-Pad27)") (class "Default")
      (node (ref "U8") (pin "27") (pinfunction "P0.22_27") (pintype "bidirectional"))
    )
    (net (code "74") (name "unconnected-(U8-P0.23-Pad28)") (class "Default")
      (node (ref "U8") (pin "28") (pinfunction "P0.23_28") (pintype "bidirectional"))
    )
    (net (code "75") (name "unconnected-(U8-P0.24-Pad29)") (class "Default")
      (node (ref "U8") (pin "29") (pinfunction "P0.24_29") (pintype "bidirectional"))
    )
    (net (code "76") (name "unconnected-(U8-P0.25-Pad37)") (class "Default")
      (node (ref "U8") (pin "37") (pinfunction "P0.25_37") (pintype "bidirectional"))
    )
  )
)
